# Battery_charger.net
KiCad netlist of a schematic drawn in Altium Designer
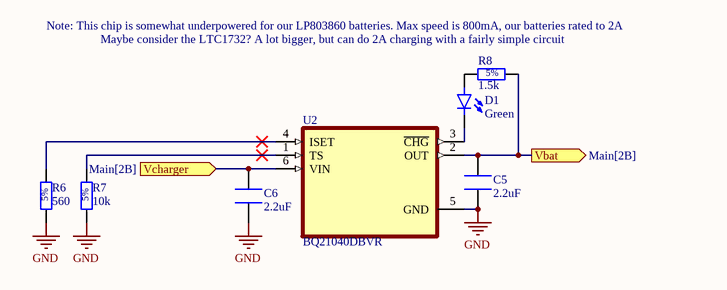
[diagram p0: Battery charger.SchDoc]

(export (version "E")
  (design (tool "Eeschema 10.0.6"))
  (components
    (comp (ref "C5")
      (value "2.2uF")
      (footprint "APSS Prototype Parts:CAPACITOR_0805_2012M-70N")
      (fields
        (field (name "TOLERANCE") "±10%")
        (field (name "MF PART NO.") "C0805C225K8PACTU")
        (field (name "APSS STANDARD PART") "APSS Standard")
      )
      (libsource (lib "APSS Prototype Parts") (part "C0805C225K8PACTU"))
    )
    (comp (ref "C6")
      (value "2.2uF")
      (footprint "APSS Prototype Parts:CAPACITOR_0805_2012M-70N")
      (fields
        (field (name "TOLERANCE") "±10%")
        (field (name "MF PART NO.") "C0805C225K8PACTU")
        (field (name "APSS STANDARD PART") "APSS Standard")
      )
      (libsource (lib "APSS Prototype Parts") (part "C0805C225K8PACTU"))
    )
    (comp (ref "D1")
      (value "LTST-C190 Series")
      (footprint "APSS Prototype Parts:LED_0603_1608M_0.80mm")
      (description "Diode - LED, 0603")
      (fields
        (field (name "MF PART NO.") "LTST-C190KGKT")
        (field (name "COLOUR") "Green")
        (field (name "APSS STANDARD PART") "APSS Standard")
      )
      (libsource (lib "APSS Prototype Parts") (part "LTST-C190 Series"))
    )
    (comp (ref "R6")
      (value "560")
      (footprint "APSS Flight Parts:Resistor_0805_2012M-50N")
      (fields
        (field (name "TOLERANCE") "5%")
        (field (name "POWER") "1/8W")
        (field (name "MF PART NO.") "RMCF0805JT560R")
      )
      (libsource (lib "APSS Prototype Parts") (part "RMCF0805JT Series"))
    )
    (comp (ref "R7")
      (value "10k")
      (footprint "APSS Flight Parts:Resistor_0805_2012M-50N")
      (fields
        (field (name "TOLERANCE") "5%")
        (field (name "POWER") "1/8W")
        (field (name "MF PART NO.") "RMCF0805JT10K0")
      )
      (libsource (lib "APSS Prototype Parts") (part "RMCF0805JT Series"))
    )
    (comp (ref "R8")
      (value "1.5k")
      (footprint "APSS Flight Parts:Resistor_0805_2012M-50N")
      (fields
        (field (name "TOLERANCE") "5%")
        (field (name "POWER") "1/8W")
        (field (name "MF PART NO.") "RMCF0805JT1K50")
      )
      (libsource (lib "") (part "RMCF0805JT Series_1"))
    )
    (comp (ref "U2")
      (value "BQ21040DBVR")
      (footprint "SOT95P280X145-6N")
      (description "1-cell, 0.8-A Li-ion and Li-polymer battery charger")
      (fields (field (name "MF") "Texas Instruments"))
      (libsource (lib "BQ21040DBVR") (part "BQ21040DBVR"))
    )
  )
  (nets
    (net (code "1") (name "/Vbat") (class "Default")
      (node (ref "C5") (pin "2") (pinfunction "2_2") (pintype "passive"))
      (node (ref "R8") (pin "2") (pinfunction "2_2") (pintype "passive"))
      (node (ref "U2") (pin "2") (pinfunction "OUT_2") (pintype "output"))
    )
    (net (code "2") (name "/Vcharger") (class "Default")
      (node (ref "C6") (pin "2") (pinfunction "2_2") (pintype "passive"))
      (node (ref "U2") (pin "6") (pinfunction "VIN_6") (pintype "input"))
    )
    (net (code "3") (name "GND") (class "Default")
      (node (ref "C5") (pin "1") (pinfunction "1_1") (pintype "passive"))
      (node (ref "C6") (pin "1") (pinfunction "1_1") (pintype "passive"))
      (node (ref "R6") (pin "1") (pinfunction "1_1") (pintype "passive"))
      (node (ref "R7") (pin "1") (pinfunction "1_1") (pintype "passive"))
      (node (ref "U2") (pin "5") (pinfunction "GND_5") (pintype "power_in"))
    )
    (net (code "4") (name "Net-(D1-PadA)") (class "Default")
      (node (ref "D1") (pin "A") (pinfunction "A_A") (pintype "passive"))
      (node (ref "R8") (pin "1") (pinfunction "1_1") (pintype "passive"))
    )
    (net (code "5") (name "Net-(U2-ISET)") (class "Default")
      (node (ref "R6") (pin "2") (pinfunction "2_2") (pintype "passive"))
      (node (ref "U2") (pin "4") (pinfunction "ISET_4") (pintype "input"))
    )
    (net (code "6") (name "Net-(U2-TS)") (class "Default")
      (node (ref "R7") (pin "2") (pinfunction "2_2") (pintype "passive"))
      (node (ref "U2") (pin "1") (pinfunction "TS_1") (pintype "input"))
    )
    (net (code "7") (name "Net-(U2-~{CHG})") (class "Default")
      (node (ref "D1") (pin "C") (pinfunction "C_C") (pintype "passive"))
      (node (ref "U2") (pin "3") (pinfunction "~{CHG}_3") (pintype "output"))
    )
  )
)
